# schematic.net
KiCad netlist of a schematic drawn in EAGLE
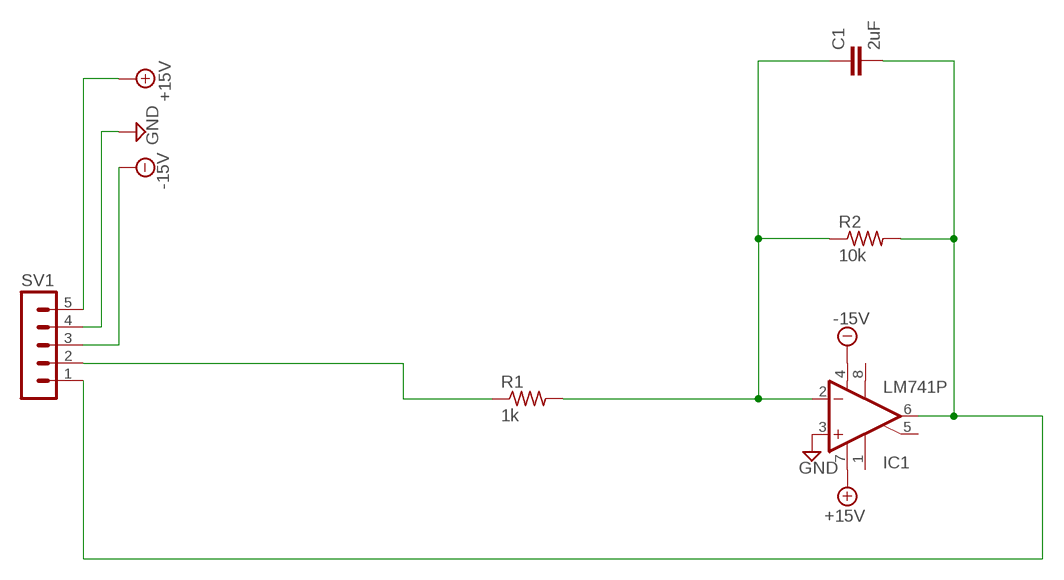
[diagram p0: schematic, sheet 1]

(export (version "E")
  (design (tool "Eeschema 10.0.6"))
  (components
    (comp (ref "C1")
      (value "2uF")
      (footprint "eagle-import:C0603")
      (libsource (lib "eagle-import") (part "C-EUC0603"))
    )
    (comp (ref "IC1")
      (value "LM741P")
      (footprint "eagle-import:DIL08")
      (libsource (lib "eagle-import") (part "741PLM"))
    )
    (comp (ref "R1")
      (value "1k")
      (footprint "eagle-import:R0603")
      (libsource (lib "eagle-import") (part "R-US_R0603"))
    )
    (comp (ref "R2")
      (value "10k")
      (footprint "eagle-import:R0603")
      (libsource (lib "eagle-import") (part "R-US_R0603"))
    )
    (comp (ref "SV1")
      (value "MA05-1")
      (footprint "eagle-import:MA05-1")
      (libsource (lib "eagle-import") (part "MA05-1"))
    )
  )
  (nets
    (net (code "1") (name "+15V") (class "Default")
      (node (ref "IC1") (pin "7") (pinfunction "V+_7") (pintype "power_in"))
      (node (ref "SV1") (pin "5") (pinfunction "5_5") (pintype "passive"))
    )
    (net (code "2") (name "-15V") (class "Default")
      (node (ref "IC1") (pin "4") (pinfunction "V-_4") (pintype "power_in"))
      (node (ref "SV1") (pin "3") (pinfunction "3_3") (pintype "passive"))
    )
    (net (code "3") (name "GND") (class "Default")
      (node (ref "IC1") (pin "3") (pinfunction "+IN_3") (pintype "input"))
      (node (ref "SV1") (pin "4") (pinfunction "4_4") (pintype "passive"))
    )
    (net (code "4") (name "Net-(IC1--IN)") (class "Default")
      (node (ref "C1") (pin "1") (pinfunction "1_1") (pintype "passive"))
      (node (ref "IC1") (pin "2") (pinfunction "-IN_2") (pintype "input"))
      (node (ref "R1") (pin "2") (pinfunction "2_2") (pintype "passive"))
      (node (ref "R2") (pin "1") (pinfunction "1_1") (pintype "passive"))
    )
    (net (code "5") (name "Net-(IC1-OUT)") (class "Default")
      (node (ref "C1") (pin "2") (pinfunction "2_2") (pintype "passive"))
      (node (ref "IC1") (pin "6") (pinfunction "OUT_6") (pintype "output"))
      (node (ref "R2") (pin "2") (pinfunction "2_2") (pintype "passive"))
      (node (ref "SV1") (pin "1") (pinfunction "1_1") (pintype "passive"))
    )
    (net (code "6") (name "Net-(R1-Pad1)") (class "Default")
      (node (ref "R1") (pin "1") (pinfunction "1_1") (pintype "passive"))
      (node (ref "SV1") (pin "2") (pinfunction "2_2") (pintype "passive"))
    )
    (net (code "7") (name "unconnected-(IC1-ON1-Pad1)") (class "Default")
      (node (ref "IC1") (pin "1") (pinfunction "ON1_1") (pintype "passive"))
    )
    (net (code "8") (name "unconnected-(IC1-ON2-Pad5)") (class "Default")
      (node (ref "IC1") (pin "5") (pinfunction "ON2_5") (pintype "passive"))
    )
    (net (code "9") (name "unconnected-(IC1-OPT-Pad8)") (class "Default")
      (node (ref "IC1") (pin "8") (pinfunction "OPT_8") (pintype "passive"))
    )
  )
)
